# Dimmer.net
KiCad netlist of a schematic drawn in Altium Designer
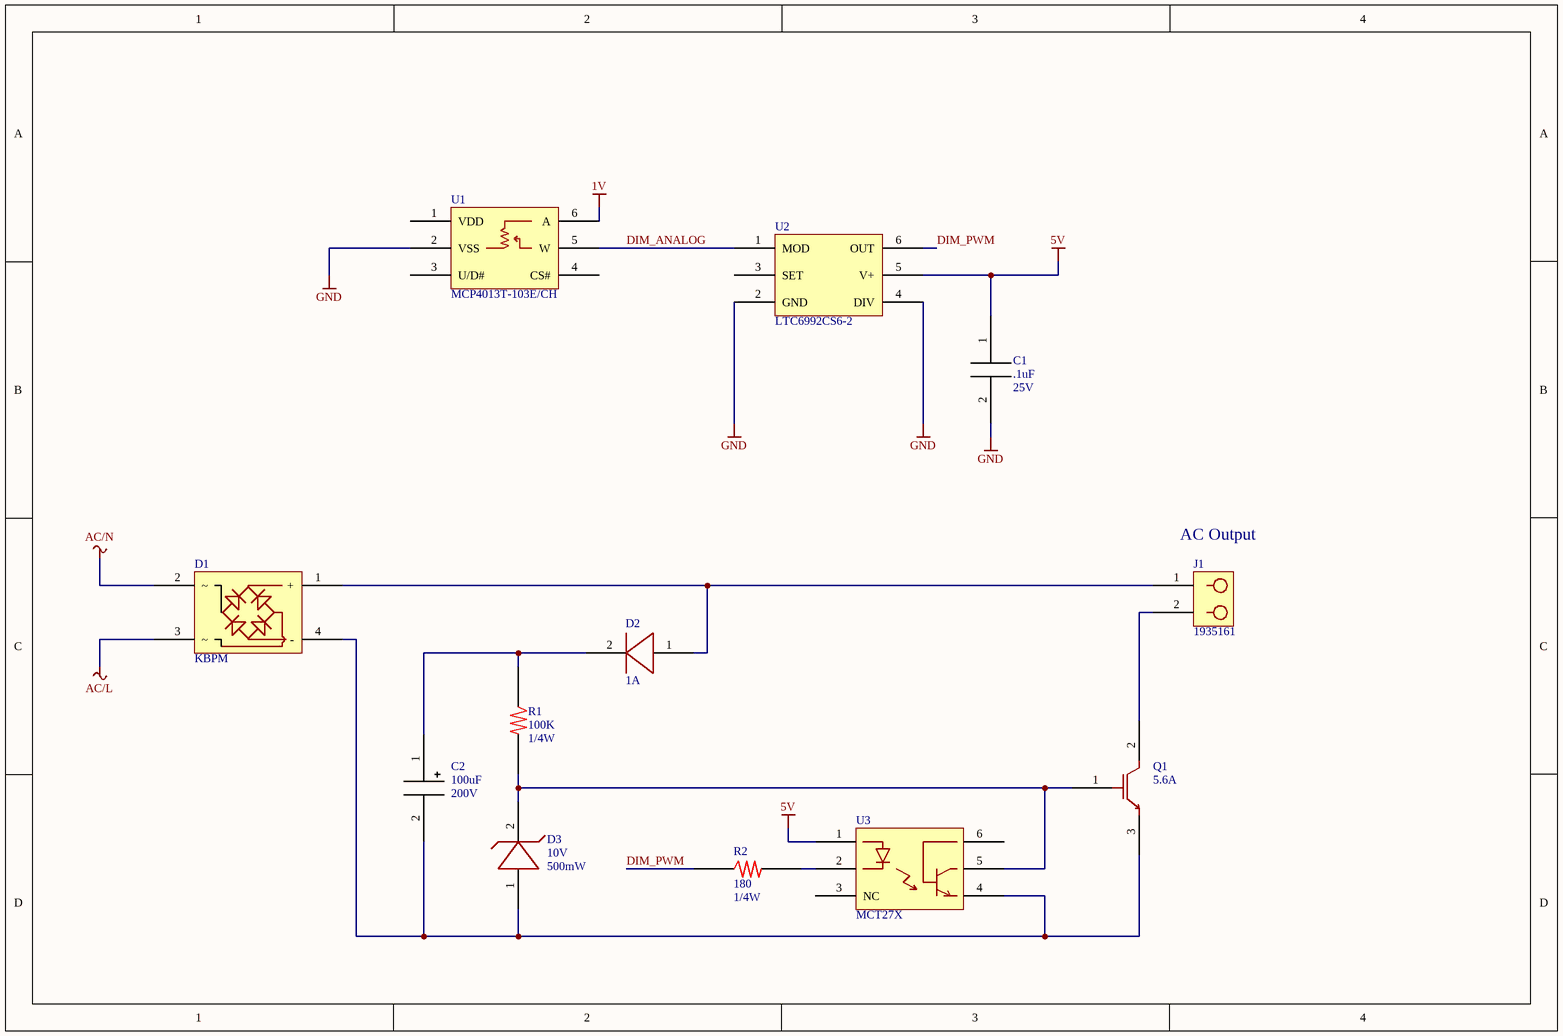
[diagram p0: Dimmer.SchDoc]

(export (version "E")
  (design (tool "Eeschema 10.0.6"))
  (components
    (comp (ref "C1")
      (value ".1uF")
      (footprint "1206")
      (fields (field (name "RATING") "25V") (field (name "Comment") "CAP"))
      (libsource (lib "SeniorProject") (part "C_CAP_1206"))
    )
    (comp (ref "C2")
      (value "100uF")
      (footprint "CAPM7")
      (fields (field (name "RATING") "200V") (field (name "Comment") "CAP"))
      (libsource (lib "SeniorProject") (part "C_CAPP_CAPM7"))
    )
    (comp (ref "D1") (value "KBPM") (footprint "KBPM") (libsource (lib "SeniorProject") (part "D_KBPM_KBMP")))
    (comp (ref "D2")
      (value "DIODE")
      (footprint "DO41")
      (fields (field (name "RATING") "1A"))
      (libsource (lib "SeniorProject") (part "D_DIODE_DO41"))
    )
    (comp (ref "D3")
      (value "10V")
      (footprint "DO35")
      (fields (field (name "RATING") "500mW") (field (name "Comment") "ZENER"))
      (libsource (lib "SeniorProject") (part "D_ZENER_DO35"))
    )
    (comp (ref "J1")
      (value "1935161")
      (footprint "1935161")
      (libsource (lib "SeniorProject") (part "J_2POSTERM_1935161"))
    )
    (comp (ref "Q1")
      (value "Q_IRF510_TO-220AB")
      (footprint "TO-220AB")
      (fields (field (name "RATING") "5.6A"))
      (libsource (lib "SeniorProject") (part "Q_IRF510_TO-220AB"))
    )
    (comp (ref "R1")
      (value "100K")
      (footprint "1206")
      (fields (field (name "RATING") "1/4W") (field (name "Comment") "R_RES_1206"))
      (libsource (lib "SeniorProject") (part "R_RES_1206"))
    )
    (comp (ref "R2")
      (value "180")
      (footprint "1206")
      (fields (field (name "RATING") "1/4W") (field (name "Comment") "R_RES_1206"))
      (libsource (lib "SeniorProject") (part "R_RES_1206"))
    )
    (comp (ref "U1")
      (value "MCP4013T-103E/CH")
      (footprint "SOT23-6")
      (libsource (lib "SeniorProject") (part "U_ MCP4013T-103E/CH_SOT23-6"))
    )
    (comp (ref "U2")
      (value "LTC6992CS6-2")
      (footprint "SOT23-6")
      (libsource (lib "SeniorProject") (part "U_LTC6992CS6-2_SOT23-6"))
    )
    (comp (ref "U3")
      (value "MCT27X")
      (footprint "DIP6")
      (libsource (lib "SeniorProject") (part "U_MCT27X_DIP6"))
    )
  )
  (nets
    (net (code "1") (name "/DIM_ANALOG") (class "Default")
      (node (ref "U1") (pin "5") (pinfunction "W_5") (pintype "passive"))
      (node (ref "U2") (pin "1") (pinfunction "MOD_1") (pintype "passive"))
    )
    (net (code "2") (name "/DIM_PWM") (class "Default")
      (node (ref "R2") (pin "1") (pintype "passive"))
      (node (ref "U2") (pin "6") (pinfunction "OUT_6") (pintype "passive"))
    )
    (net (code "3") (name "1V") (class "Default")
      (node (ref "U1") (pin "6") (pinfunction "A_6") (pintype "passive"))
    )
    (net (code "4") (name "5V") (class "Default")
      (node (ref "C1") (pin "1") (pintype "passive"))
      (node (ref "U2") (pin "5") (pinfunction "V+_5") (pintype "passive"))
      (node (ref "U3") (pin "1") (pintype "passive"))
    )
    (net (code "5") (name "AC{slash}L") (class "Default")
      (node (ref "D1") (pin "3") (pinfunction "~_3") (pintype "passive"))
    )
    (net (code "6") (name "AC{slash}N") (class "Default")
      (node (ref "D1") (pin "2") (pinfunction "~_2") (pintype "power_in"))
    )
    (net (code "7") (name "GND") (class "Default")
      (node (ref "C1") (pin "2") (pintype "passive"))
      (node (ref "U1") (pin "2") (pinfunction "VSS_2") (pintype "passive"))
      (node (ref "U2") (pin "2") (pinfunction "GND_2") (pintype "passive"))
      (node (ref "U2") (pin "4") (pinfunction "DIV_4") (pintype "passive"))
    )
    (net (code "8") (name "Net-(C2-Pad1)") (class "Default")
      (node (ref "C2") (pin "1") (pintype "passive"))
      (node (ref "D2") (pin "2") (pintype "passive"))
      (node (ref "R1") (pin "1") (pintype "passive"))
    )
    (net (code "9") (name "Net-(D1-+)") (class "Default")
      (node (ref "D1") (pin "1") (pinfunction "+_1") (pintype "passive"))
      (node (ref "D2") (pin "1") (pintype "passive"))
      (node (ref "J1") (pin "1") (pintype "passive"))
    )
    (net (code "10") (name "Net-(D1--)") (class "Default")
      (node (ref "C2") (pin "2") (pintype "passive"))
      (node (ref "D1") (pin "4") (pinfunction "-_4") (pintype "passive"))
      (node (ref "D3") (pin "1") (pintype "passive"))
      (node (ref "Q1") (pin "3") (pinfunction "S_3") (pintype "passive"))
      (node (ref "U3") (pin "4") (pintype "passive"))
    )
    (net (code "11") (name "Net-(Q1-D)") (class "Default")
      (node (ref "J1") (pin "2") (pintype "passive"))
      (node (ref "Q1") (pin "2") (pinfunction "D_2") (pintype "passive"))
    )
    (net (code "12") (name "Net-(Q1-G)") (class "Default")
      (node (ref "D3") (pin "2") (pintype "passive"))
      (node (ref "Q1") (pin "1") (pinfunction "G_1") (pintype "passive"))
      (node (ref "R1") (pin "2") (pintype "passive"))
      (node (ref "U3") (pin "5") (pintype "passive"))
    )
    (net (code "13") (name "Net-(R2-Pad2)") (class "Default")
      (node (ref "R2") (pin "2") (pintype "passive"))
      (node (ref "U3") (pin "2") (pintype "passive"))
    )
    (net (code "14") (name "unconnected-(U1-CS#-Pad4)") (class "Default")
      (node (ref "U1") (pin "4") (pinfunction "CS#_4") (pintype "passive"))
    )
    (net (code "15") (name "unconnected-(U1-U{slash}D#-Pad3)") (class "Default")
      (node (ref "U1") (pin "3") (pinfunction "U/D#_3") (pintype "passive"))
    )
    (net (code "16") (name "unconnected-(U1-VDD-Pad1)") (class "Default")
      (node (ref "U1") (pin "1") (pinfunction "VDD_1") (pintype "power_in"))
    )
    (net (code "17") (name "unconnected-(U2-SET-Pad3)") (class "Default")
      (node (ref "U2") (pin "3") (pinfunction "SET_3") (pintype "passive"))
    )
    (net (code "18") (name "unconnected-(U3-NC-Pad3)") (class "Default")
      (node (ref "U3") (pin "3") (pinfunction "NC_3") (pintype "passive"))
    )
    (net (code "19") (name "unconnected-(U3-Pad6)") (class "Default")
      (node (ref "U3") (pin "6") (pintype "passive"))
    )
  )
)
